# 28-pin_SOIC_TSSOP.net
KiCad netlist of a schematic drawn in EAGLE
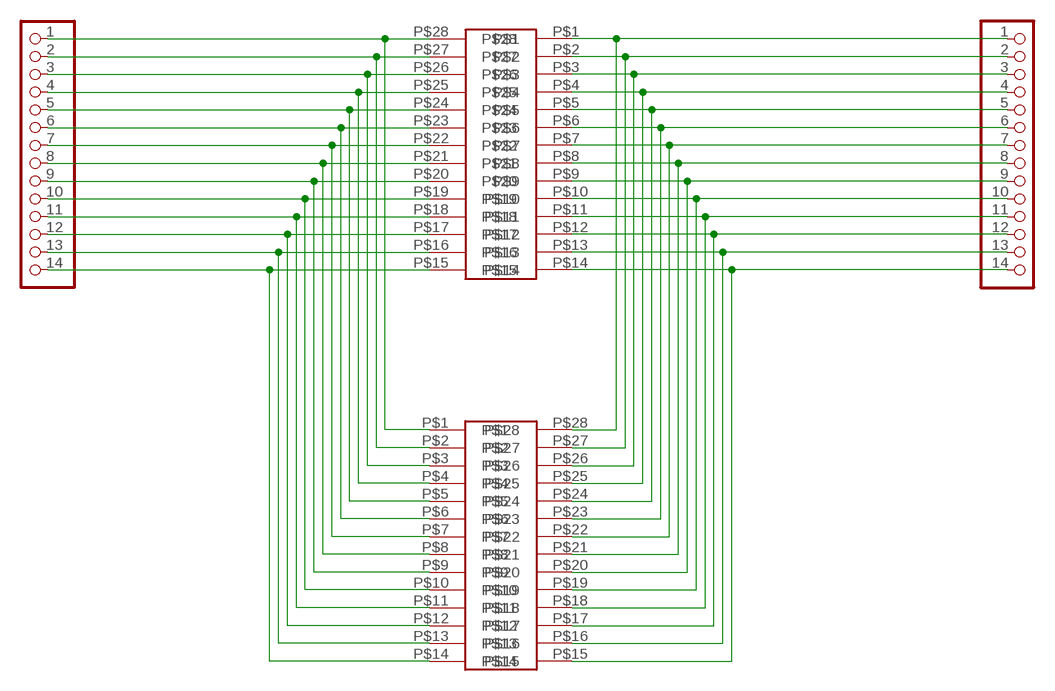
[diagram p0: schematic, sheet 1]

(export (version "E")
  (design (tool "Eeschema 10.0.6"))
  (components
    (comp (ref "JP1")
      (value "PADS-14")
      (footprint "eagle-import:PADS-14")
      (libsource (lib "eagle-import") (part "PADS-14"))
    )
    (comp (ref "JP2")
      (value "PADS-14")
      (footprint "eagle-import:PADS-14")
      (libsource (lib "eagle-import") (part "PADS-14"))
    )
    (comp (ref "U$1")
      (value "28-PINSOIC-NW")
      (footprint "eagle-import:SO28-NW")
      (libsource (lib "eagle-import") (part "28-PINSOIC-NW"))
    )
    (comp (ref "U$2")
      (value "28-PINTSSOP-NW")
      (footprint "eagle-import:TSSOP28-NW")
      (libsource (lib "eagle-import") (part "28-PINTSSOP-NW"))
    )
  )
  (nets
    (net (code "1") (name "Net-(JP1-Pad1)") (class "Default")
      (node (ref "JP1") (pin "1") (pinfunction "1_1") (pintype "passive"))
      (node (ref "U$1") (pin "P$1") (pinfunction "P$1_P$1") (pintype "bidirectional"))
      (node (ref "U$2") (pin "P$28") (pinfunction "P$28_P$28") (pintype "bidirectional"))
    )
    (net (code "2") (name "Net-(JP1-Pad2)") (class "Default")
      (node (ref "JP1") (pin "2") (pinfunction "2_2") (pintype "passive"))
      (node (ref "U$1") (pin "P$2") (pinfunction "P$2_P$2") (pintype "bidirectional"))
      (node (ref "U$2") (pin "P$27") (pinfunction "P$27_P$27") (pintype "bidirectional"))
    )
    (net (code "3") (name "Net-(JP1-Pad3)") (class "Default")
      (node (ref "JP1") (pin "3") (pinfunction "3_3") (pintype "passive"))
      (node (ref "U$1") (pin "P$3") (pinfunction "P$3_P$3") (pintype "bidirectional"))
      (node (ref "U$2") (pin "P$26") (pinfunction "P$26_P$26") (pintype "bidirectional"))
    )
    (net (code "4") (name "Net-(JP1-Pad4)") (class "Default")
      (node (ref "JP1") (pin "4") (pinfunction "4_4") (pintype "passive"))
      (node (ref "U$1") (pin "P$4") (pinfunction "P$4_P$4") (pintype "bidirectional"))
      (node (ref "U$2") (pin "P$25") (pinfunction "P$25_P$25") (pintype "bidirectional"))
    )
    (net (code "5") (name "Net-(JP1-Pad5)") (class "Default")
      (node (ref "JP1") (pin "5") (pinfunction "5_5") (pintype "passive"))
      (node (ref "U$1") (pin "P$5") (pinfunction "P$5_P$5") (pintype "bidirectional"))
      (node (ref "U$2") (pin "P$24") (pinfunction "P$24_P$24") (pintype "bidirectional"))
    )
    (net (code "6") (name "Net-(JP1-Pad6)") (class "Default")
      (node (ref "JP1") (pin "6") (pinfunction "6_6") (pintype "passive"))
      (node (ref "U$1") (pin "P$6") (pinfunction "P$6_P$6") (pintype "bidirectional"))
      (node (ref "U$2") (pin "P$23") (pinfunction "P$23_P$23") (pintype "bidirectional"))
    )
    (net (code "7") (name "Net-(JP1-Pad7)") (class "Default")
      (node (ref "JP1") (pin "7") (pinfunction "7_7") (pintype "passive"))
      (node (ref "U$1") (pin "P$7") (pinfunction "P$7_P$7") (pintype "bidirectional"))
      (node (ref "U$2") (pin "P$22") (pinfunction "P$22_P$22") (pintype "bidirectional"))
    )
    (net (code "8") (name "Net-(JP1-Pad8)") (class "Default")
      (node (ref "JP1") (pin "8") (pinfunction "8_8") (pintype "passive"))
      (node (ref "U$1") (pin "P$8") (pinfunction "P$8_P$8") (pintype "bidirectional"))
      (node (ref "U$2") (pin "P$21") (pinfunction "P$21_P$21") (pintype "bidirectional"))
    )
    (net (code "9") (name "Net-(JP1-Pad9)") (class "Default")
      (node (ref "JP1") (pin "9") (pinfunction "9_9") (pintype "passive"))
      (node (ref "U$1") (pin "P$9") (pinfunction "P$9_P$9") (pintype "bidirectional"))
      (node (ref "U$2") (pin "P$20") (pinfunction "P$20_P$20") (pintype "bidirectional"))
    )
    (net (code "10") (name "Net-(JP1-Pad10)") (class "Default")
      (node (ref "JP1") (pin "10") (pinfunction "10_10") (pintype "passive"))
      (node (ref "U$1") (pin "P$10") (pinfunction "P$10_P$10") (pintype "bidirectional"))
      (node (ref "U$2") (pin "P$19") (pinfunction "P$19_P$19") (pintype "bidirectional"))
    )
    (net (code "11") (name "Net-(JP1-Pad11)") (class "Default")
      (node (ref "JP1") (pin "11") (pinfunction "11_11") (pintype "passive"))
      (node (ref "U$1") (pin "P$11") (pinfunction "P$11_P$11") (pintype "bidirectional"))
      (node (ref "U$2") (pin "P$18") (pinfunction "P$18_P$18") (pintype "bidirectional"))
    )
    (net (code "12") (name "Net-(JP1-Pad12)") (class "Default")
      (node (ref "JP1") (pin "12") (pinfunction "12_12") (pintype "passive"))
      (node (ref "U$1") (pin "P$12") (pinfunction "P$12_P$12") (pintype "bidirectional"))
      (node (ref "U$2") (pin "P$17") (pinfunction "P$17_P$17") (pintype "bidirectional"))
    )
    (net (code "13") (name "Net-(JP1-Pad13)") (class "Default")
      (node (ref "JP1") (pin "13") (pinfunction "13_13") (pintype "passive"))
      (node (ref "U$1") (pin "P$13") (pinfunction "P$13_P$13") (pintype "bidirectional"))
      (node (ref "U$2") (pin "P$16") (pinfunction "P$16_P$16") (pintype "bidirectional"))
    )
    (net (code "14") (name "Net-(JP1-Pad14)") (class "Default")
      (node (ref "JP1") (pin "14") (pinfunction "14_14") (pintype "passive"))
      (node (ref "U$1") (pin "P$14") (pinfunction "P$14_P$14") (pintype "bidirectional"))
      (node (ref "U$2") (pin "P$15") (pinfunction "P$15_P$15") (pintype "bidirectional"))
    )
    (net (code "15") (name "Net-(JP2-Pad1)") (class "Default")
      (node (ref "JP2") (pin "1") (pinfunction "1_1") (pintype "passive"))
      (node (ref "U$1") (pin "P$28") (pinfunction "P$28_P$28") (pintype "bidirectional"))
      (node (ref "U$2") (pin "P$1") (pinfunction "P$1_P$1") (pintype "bidirectional"))
    )
    (net (code "16") (name "Net-(JP2-Pad2)") (class "Default")
      (node (ref "JP2") (pin "2") (pinfunction "2_2") (pintype "passive"))
      (node (ref "U$1") (pin "P$27") (pinfunction "P$27_P$27") (pintype "bidirectional"))
      (node (ref "U$2") (pin "P$2") (pinfunction "P$2_P$2") (pintype "bidirectional"))
    )
    (net (code "17") (name "Net-(JP2-Pad3)") (class "Default")
      (node (ref "JP2") (pin "3") (pinfunction "3_3") (pintype "passive"))
      (node (ref "U$1") (pin "P$26") (pinfunction "P$26_P$26") (pintype "bidirectional"))
      (node (ref "U$2") (pin "P$3") (pinfunction "P$3_P$3") (pintype "bidirectional"))
    )
    (net (code "18") (name "Net-(JP2-Pad4)") (class "Default")
      (node (ref "JP2") (pin "4") (pinfunction "4_4") (pintype "passive"))
      (node (ref "U$1") (pin "P$25") (pinfunction "P$25_P$25") (pintype "bidirectional"))
      (node (ref "U$2") (pin "P$4") (pinfunction "P$4_P$4") (pintype "bidirectional"))
    )
    (net (code "19") (name "Net-(JP2-Pad5)") (class "Default")
      (node (ref "JP2") (pin "5") (pinfunction "5_5") (pintype "passive"))
      (node (ref "U$1") (pin "P$24") (pinfunction "P$24_P$24") (pintype "bidirectional"))
      (node (ref "U$2") (pin "P$5") (pinfunction "P$5_P$5") (pintype "bidirectional"))
    )
    (net (code "20") (name "Net-(JP2-Pad6)") (class "Default")
      (node (ref "JP2") (pin "6") (pinfunction "6_6") (pintype "passive"))
      (node (ref "U$1") (pin "P$23") (pinfunction "P$23_P$23") (pintype "bidirectional"))
      (node (ref "U$2") (pin "P$6") (pinfunction "P$6_P$6") (pintype "bidirectional"))
    )
    (net (code "21") (name "Net-(JP2-Pad7)") (class "Default")
      (node (ref "JP2") (pin "7") (pinfunction "7_7") (pintype "passive"))
      (node (ref "U$1") (pin "P$22") (pinfunction "P$22_P$22") (pintype "bidirectional"))
      (node (ref "U$2") (pin "P$7") (pinfunction "P$7_P$7") (pintype "bidirectional"))
    )
    (net (code "22") (name "Net-(JP2-Pad8)") (class "Default")
      (node (ref "JP2") (pin "8") (pinfunction "8_8") (pintype "passive"))
      (node (ref "U$1") (pin "P$21") (pinfunction "P$21_P$21") (pintype "bidirectional"))
      (node (ref "U$2") (pin "P$8") (pinfunction "P$8_P$8") (pintype "bidirectional"))
    )
    (net (code "23") (name "Net-(JP2-Pad9)") (class "Default")
      (node (ref "JP2") (pin "9") (pinfunction "9_9") (pintype "passive"))
      (node (ref "U$1") (pin "P$20") (pinfunction "P$20_P$20") (pintype "bidirectional"))
      (node (ref "U$2") (pin "P$9") (pinfunction "P$9_P$9") (pintype "bidirectional"))
    )
    (net (code "24") (name "Net-(JP2-Pad10)") (class "Default")
      (node (ref "JP2") (pin "10") (pinfunction "10_10") (pintype "passive"))
      (node (ref "U$1") (pin "P$19") (pinfunction "P$19_P$19") (pintype "bidirectional"))
      (node (ref "U$2") (pin "P$10") (pinfunction "P$10_P$10") (pintype "bidirectional"))
    )
    (net (code "25") (name "Net-(JP2-Pad11)") (class "Default")
      (node (ref "JP2") (pin "11") (pinfunction "11_11") (pintype "passive"))
      (node (ref "U$1") (pin "P$18") (pinfunction "P$18_P$18") (pintype "bidirectional"))
      (node (ref "U$2") (pin "P$11") (pinfunction "P$11_P$11") (pintype "bidirectional"))
    )
    (net (code "26") (name "Net-(JP2-Pad12)") (class "Default")
      (node (ref "JP2") (pin "12") (pinfunction "12_12") (pintype "passive"))
      (node (ref "U$1") (pin "P$17") (pinfunction "P$17_P$17") (pintype "bidirectional"))
      (node (ref "U$2") (pin "P$12") (pinfunction "P$12_P$12") (pintype "bidirectional"))
    )
    (net (code "27") (name "Net-(JP2-Pad13)") (class "Default")
      (node (ref "JP2") (pin "13") (pinfunction "13_13") (pintype "passive"))
      (node (ref "U$1") (pin "P$16") (pinfunction "P$16_P$16") (pintype "bidirectional"))
      (node (ref "U$2") (pin "P$13") (pinfunction "P$13_P$13") (pintype "bidirectional"))
    )
    (net (code "28") (name "Net-(JP2-Pad14)") (class "Default")
      (node (ref "JP2") (pin "14") (pinfunction "14_14") (pintype "passive"))
      (node (ref "U$1") (pin "P$15") (pinfunction "P$15_P$15") (pintype "bidirectional"))
      (node (ref "U$2") (pin "P$14") (pinfunction "P$14_P$14") (pintype "bidirectional"))
    )
  )
)
